# MSP430F5528ZQFE.net
KiCad netlist of a schematic drawn in Altium Designer
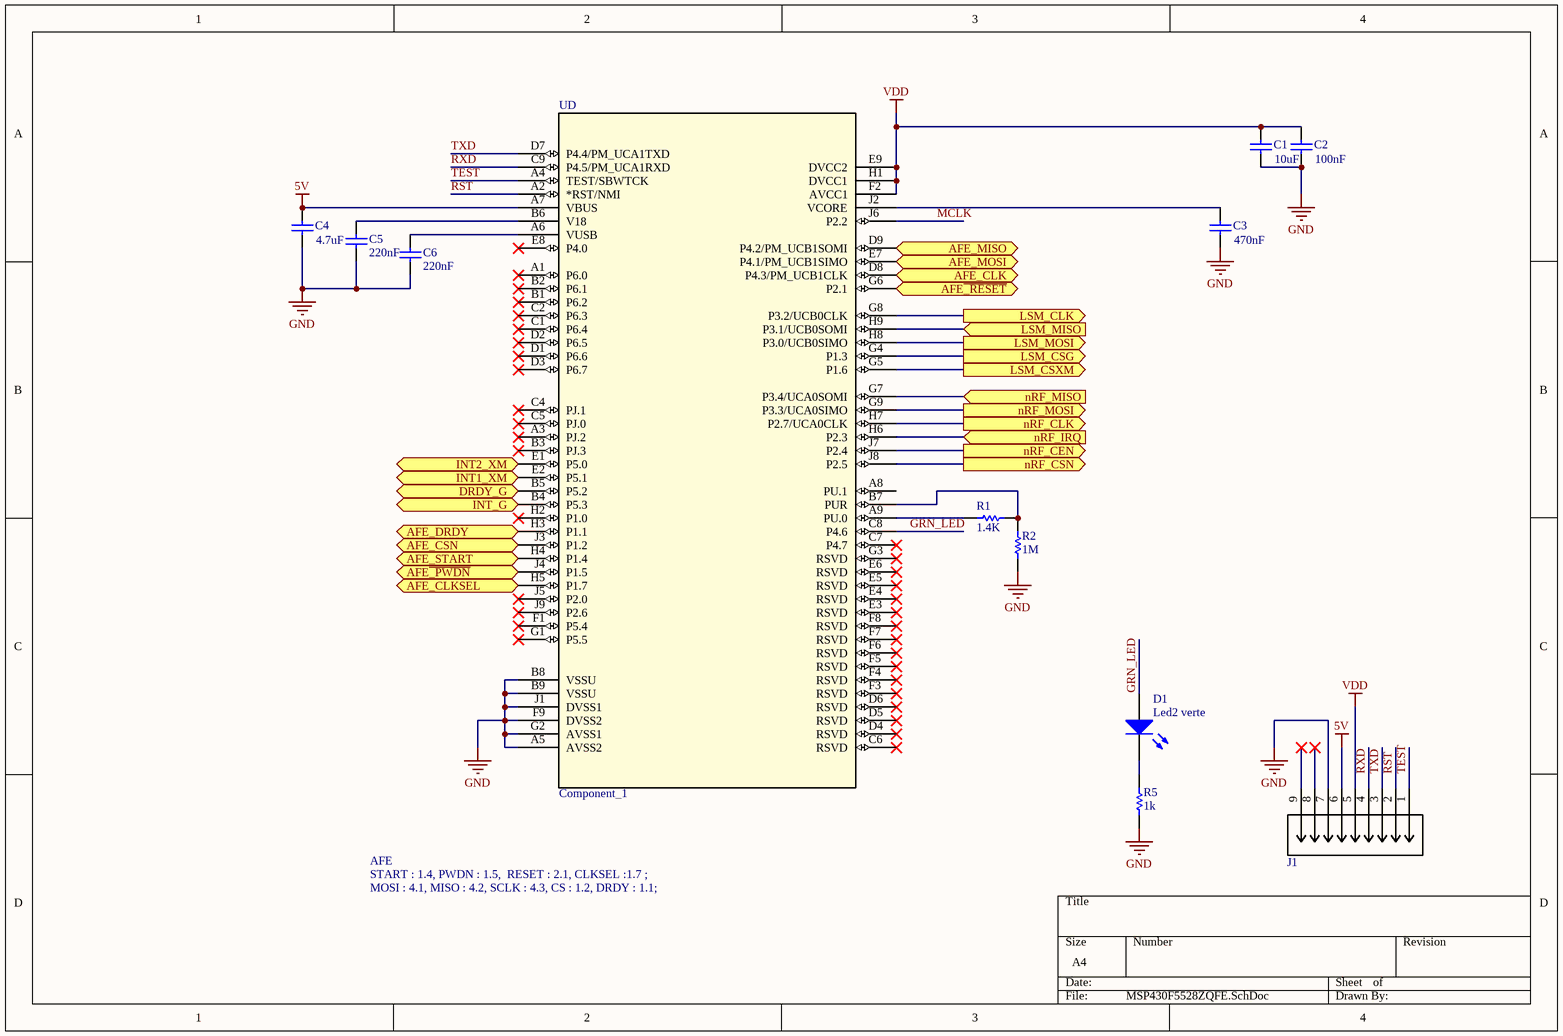
[diagram p0: MSP430F5528ZQFE.SchDoc]

(export (version "E")
  (design (tool "Eeschema 10.0.6"))
  (components
    (comp (ref "C1")
      (value "10uF")
      (footprint "0402")
      (description "Capacitor (Semiconductor SIM Model)")
      (fields (field (name "Comment") "Cap Semi") (field (name "PUBLISHER") "Altium Limited"))
      (libsource (lib "Miscellaneous Devices") (part "Cap Semi"))
    )
    (comp (ref "C2")
      (value "100nF")
      (footprint "0402")
      (description "Capacitor (Semiconductor SIM Model)")
      (fields (field (name "Comment") "Cap Semi") (field (name "PUBLISHER") "Altium Limited"))
      (libsource (lib "Miscellaneous Devices") (part "Cap Semi"))
    )
    (comp (ref "C3")
      (value "470nF")
      (footprint "0402")
      (description "Capacitor (Semiconductor SIM Model)")
      (fields (field (name "Comment") "Cap Semi") (field (name "PUBLISHER") "Altium Limited"))
      (libsource (lib "Miscellaneous Devices") (part "Cap Semi"))
    )
    (comp (ref "C4")
      (value "4.7uF")
      (footprint "0402")
      (description "Capacitor (Semiconductor SIM Model)")
      (fields (field (name "Comment") "Cap Semi") (field (name "PUBLISHER") "Altium Limited"))
      (libsource (lib "Miscellaneous Devices") (part "Cap Semi"))
    )
    (comp (ref "C5")
      (value "220nF")
      (footprint "0402")
      (description "Capacitor (Semiconductor SIM Model)")
      (fields (field (name "Comment") "Cap Semi") (field (name "PUBLISHER") "Altium Limited"))
      (libsource (lib "Miscellaneous Devices") (part "Cap Semi"))
    )
    (comp (ref "C6")
      (value "220nF")
      (footprint "0402")
      (description "Capacitor (Semiconductor SIM Model)")
      (fields (field (name "Comment") "Cap Semi") (field (name "PUBLISHER") "Altium Limited"))
      (libsource (lib "Miscellaneous Devices") (part "Cap Semi"))
    )
    (comp (ref "D1")
      (value "Led2 verte")
      (footprint "0805 (2012 metric)")
      (description "LED 2X1.2MM 570NM GN WTR CLR SMD")
      (libsource (lib "Miscellaneous Devices") (part "LED3"))
    )
    (comp (ref "J1")
      (value "FH12-7S-1SH(55)")
      (footprint "CON7_1X7_DRBF_HS")
      (description "Imported")
      (fields
        (field (name "DIGIKEYPARTNUMBER") "HFB107TR-ND")
        (field (name "COPYRIGHT") "Copyright (C) 2015 Accelerated Designs. All rights reserved")
      )
      (libsource (lib "HFB107CT-ND") (part "FH12-7S-1SH(55)"))
    )
    (comp (ref "R1")
      (value "1.4K")
      (footprint "0402")
      (description "Semiconductor Resistor")
      (fields (field (name "PUBLISHER") "Altium Limited"))
      (libsource (lib "Miscellaneous Devices") (part "Res Semi"))
    )
    (comp (ref "R2")
      (value "1M")
      (footprint "0402")
      (description "Semiconductor Resistor")
      (fields (field (name "PUBLISHER") "Altium Limited"))
      (libsource (lib "Miscellaneous Devices") (part "Res Semi"))
    )
    (comp (ref "R5")
      (value "1k")
      (footprint "0402")
      (description "Semiconductor Resistor")
      (fields (field (name "PUBLISHER") "Altium Limited"))
      (libsource (lib "Miscellaneous Devices") (part "Res Semi"))
    )
    (comp (ref "UD")
      (value "Component_1")
      (footprint "MSP430F5528ZQFE")
      (libsource (lib "MSP430F5528ZQFE") (part "Component_1"))
    )
  )
  (nets
    (net (code "1") (name "/AFE_CLK") (class "Default")
      (node (ref "UD") (pin "D8") (pinfunction "P4.3/PM_UCB1CLK_D8") (pintype "bidirectional"))
    )
    (net (code "2") (name "/AFE_CLKSEL") (class "Default")
      (node (ref "UD") (pin "H5") (pinfunction "P1.7_H5") (pintype "bidirectional"))
    )
    (net (code "3") (name "/AFE_CSN") (class "Default")
      (node (ref "UD") (pin "J3") (pinfunction "P1.2_J3") (pintype "bidirectional"))
    )
    (net (code "4") (name "/AFE_DRDY") (class "Default")
      (node (ref "UD") (pin "H3") (pinfunction "P1.1_H3") (pintype "bidirectional"))
    )
    (net (code "5") (name "/AFE_MISO") (class "Default")
      (node (ref "UD") (pin "D9") (pinfunction "P4.2/PM_UCB1SOMI_D9") (pintype "bidirectional"))
    )
    (net (code "6") (name "/AFE_MOSI") (class "Default")
      (node (ref "UD") (pin "E7") (pinfunction "P4.1/PM_UCB1SIMO_E7") (pintype "bidirectional"))
    )
    (net (code "7") (name "/AFE_START") (class "Default")
      (node (ref "UD") (pin "H4") (pinfunction "P1.4_H4") (pintype "bidirectional"))
    )
    (net (code "8") (name "/AFE~{_PWDN}") (class "Default")
      (node (ref "UD") (pin "J4") (pinfunction "P1.5_J4") (pintype "bidirectional"))
    )
    (net (code "9") (name "/AFE~{_RESET}") (class "Default")
      (node (ref "UD") (pin "G6") (pinfunction "P2.1_G6") (pintype "bidirectional"))
    )
    (net (code "10") (name "/DRDY_G") (class "Default")
      (node (ref "UD") (pin "B5") (pinfunction "P5.2_B5") (pintype "bidirectional"))
    )
    (net (code "11") (name "/GRN_LED") (class "Default")
      (node (ref "D1") (pin "1") (pinfunction "A_1") (pintype "passive"))
      (node (ref "UD") (pin "C8") (pinfunction "P4.6_C8") (pintype "bidirectional"))
    )
    (net (code "12") (name "/INT1_XM") (class "Default")
      (node (ref "UD") (pin "E2") (pinfunction "P5.1_E2") (pintype "bidirectional"))
    )
    (net (code "13") (name "/INT2_XM") (class "Default")
      (node (ref "UD") (pin "E1") (pinfunction "P5.0_E1") (pintype "bidirectional"))
    )
    (net (code "14") (name "/INT_G") (class "Default")
      (node (ref "UD") (pin "B4") (pinfunction "P5.3_B4") (pintype "bidirectional"))
    )
    (net (code "15") (name "/LSM_CLK") (class "Default")
      (node (ref "UD") (pin "G8") (pinfunction "P3.2/UCB0CLK_G8") (pintype "bidirectional"))
    )
    (net (code "16") (name "/LSM_CSG") (class "Default")
      (node (ref "UD") (pin "G4") (pinfunction "P1.3_G4") (pintype "bidirectional"))
    )
    (net (code "17") (name "/LSM_CSXM") (class "Default")
      (node (ref "UD") (pin "G5") (pinfunction "P1.6_G5") (pintype "bidirectional"))
    )
    (net (code "18") (name "/LSM_MISO") (class "Default")
      (node (ref "UD") (pin "H9") (pinfunction "P3.1/UCB0SOMI_H9") (pintype "bidirectional"))
    )
    (net (code "19") (name "/LSM_MOSI") (class "Default")
      (node (ref "UD") (pin "H8") (pinfunction "P3.0/UCB0SIMO_H8") (pintype "bidirectional"))
    )
    (net (code "20") (name "/MCLK") (class "Default")
      (node (ref "UD") (pin "J6") (pinfunction "P2.2_J6") (pintype "bidirectional"))
    )
    (net (code "21") (name "/RST") (class "Default")
      (node (ref "J1") (pin "2") (pinfunction "2_2") (pintype "passive"))
      (node (ref "UD") (pin "A2") (pinfunction "*RST/NMI_A2") (pintype "bidirectional"))
    )
    (net (code "22") (name "/RXD") (class "Default")
      (node (ref "J1") (pin "4") (pinfunction "4_4") (pintype "passive"))
      (node (ref "UD") (pin "C9") (pinfunction "P4.5/PM_UCA1RXD_C9") (pintype "bidirectional"))
    )
    (net (code "23") (name "/TEST") (class "Default")
      (node (ref "J1") (pin "1") (pinfunction "1_1") (pintype "passive"))
      (node (ref "UD") (pin "A4") (pinfunction "TEST/SBWTCK_A4") (pintype "bidirectional"))
    )
    (net (code "24") (name "/TXD") (class "Default")
      (node (ref "J1") (pin "3") (pinfunction "3_3") (pintype "passive"))
      (node (ref "UD") (pin "D7") (pinfunction "P4.4/PM_UCA1TXD_D7") (pintype "bidirectional"))
    )
    (net (code "25") (name "/nRF_CEN") (class "Default")
      (node (ref "UD") (pin "J7") (pinfunction "P2.4_J7") (pintype "bidirectional"))
    )
    (net (code "26") (name "/nRF_CLK") (class "Default")
      (node (ref "UD") (pin "H7") (pinfunction "P2.7/UCA0CLK_H7") (pintype "bidirectional"))
    )
    (net (code "27") (name "/nRF_CSN") (class "Default")
      (node (ref "UD") (pin "J8") (pinfunction "P2.5_J8") (pintype "bidirectional"))
    )
    (net (code "28") (name "/nRF_IRQ") (class "Default")
      (node (ref "UD") (pin "H6") (pinfunction "P2.3_H6") (pintype "bidirectional"))
    )
    (net (code "29") (name "/nRF_MISO") (class "Default")
      (node (ref "UD") (pin "G7") (pinfunction "P3.4/UCA0SOMI_G7") (pintype "bidirectional"))
    )
    (net (code "30") (name "/nRF_MOSI") (class "Default")
      (node (ref "UD") (pin "G9") (pinfunction "P3.3/UCA0SIMO_G9") (pintype "bidirectional"))
    )
    (net (code "31") (name "5V") (class "Default")
      (node (ref "C4") (pin "1") (pinfunction "1_1") (pintype "passive"))
      (node (ref "J1") (pin "6") (pinfunction "6_6") (pintype "passive"))
      (node (ref "UD") (pin "A7") (pinfunction "VBUS_A7") (pintype "power_in"))
    )
    (net (code "32") (name "GND") (class "Default")
      (node (ref "C1") (pin "2") (pinfunction "2_2") (pintype "passive"))
      (node (ref "C2") (pin "2") (pinfunction "2_2") (pintype "passive"))
      (node (ref "C3") (pin "2") (pinfunction "2_2") (pintype "passive"))
      (node (ref "C4") (pin "2") (pinfunction "2_2") (pintype "passive"))
      (node (ref "C5") (pin "1") (pinfunction "1_1") (pintype "passive"))
      (node (ref "C6") (pin "1") (pinfunction "1_1") (pintype "passive"))
      (node (ref "J1") (pin "7") (pinfunction "7_7") (pintype "passive"))
      (node (ref "R2") (pin "2") (pinfunction "2_2") (pintype "passive"))
      (node (ref "R5") (pin "2") (pinfunction "2_2") (pintype "passive"))
      (node (ref "UD") (pin "A5") (pinfunction "AVSS2_A5") (pintype "power_in"))
      (node (ref "UD") (pin "B8") (pinfunction "VSSU_B8") (pintype "power_in"))
      (node (ref "UD") (pin "B9") (pinfunction "VSSU_B9") (pintype "power_in"))
      (node (ref "UD") (pin "F9") (pinfunction "DVSS2_F9") (pintype "power_in"))
      (node (ref "UD") (pin "G2") (pinfunction "AVSS1_G2") (pintype "power_in"))
      (node (ref "UD") (pin "J1") (pinfunction "DVSS1_J1") (pintype "power_in"))
    )
    (net (code "33") (name "Net-(D1-K)") (class "Default")
      (node (ref "D1") (pin "2") (pinfunction "K_2") (pintype "passive"))
      (node (ref "R5") (pin "1") (pinfunction "1_1") (pintype "passive"))
    )
    (net (code "34") (name "Net-(UD-PU.0)") (class "Default")
      (node (ref "R1") (pin "2") (pinfunction "2_2") (pintype "passive"))
      (node (ref "UD") (pin "A9") (pinfunction "PU.0_A9") (pintype "bidirectional"))
    )
    (net (code "35") (name "Net-(UD-PUR)") (class "Default")
      (node (ref "R1") (pin "1") (pinfunction "1_1") (pintype "passive"))
      (node (ref "R2") (pin "1") (pinfunction "1_1") (pintype "passive"))
      (node (ref "UD") (pin "B7") (pinfunction "PUR_B7") (pintype "bidirectional"))
    )
    (net (code "36") (name "Net-(UD-V18)") (class "Default")
      (node (ref "C5") (pin "2") (pinfunction "2_2") (pintype "passive"))
      (node (ref "UD") (pin "B6") (pinfunction "V18_B6") (pintype "power_in"))
    )
    (net (code "37") (name "Net-(UD-VCORE)") (class "Default")
      (node (ref "C3") (pin "1") (pinfunction "1_1") (pintype "passive"))
      (node (ref "UD") (pin "J2") (pinfunction "VCORE_J2") (pintype "power_in"))
    )
    (net (code "38") (name "Net-(UD-VUSB)") (class "Default")
      (node (ref "C6") (pin "2") (pinfunction "2_2") (pintype "passive"))
      (node (ref "UD") (pin "A6") (pinfunction "VUSB_A6") (pintype "power_in"))
    )
    (net (code "39") (name "VDD") (class "Default")
      (node (ref "C1") (pin "1") (pinfunction "1_1") (pintype "passive"))
      (node (ref "C2") (pin "1") (pinfunction "1_1") (pintype "passive"))
      (node (ref "J1") (pin "5") (pinfunction "5_5") (pintype "passive"))
      (node (ref "UD") (pin "E9") (pinfunction "DVCC2_E9") (pintype "power_in"))
      (node (ref "UD") (pin "F2") (pinfunction "AVCC1_F2") (pintype "power_in"))
      (node (ref "UD") (pin "H1") (pinfunction "DVCC1_H1") (pintype "power_in"))
    )
    (net (code "40") (name "unconnected-(J1-Pad8)") (class "Default")
      (node (ref "J1") (pin "8") (pinfunction "8_8") (pintype "passive+no_connect"))
    )
    (net (code "41") (name "unconnected-(J1-Pad9)") (class "Default")
      (node (ref "J1") (pin "9") (pinfunction "9_9") (pintype "passive+no_connect"))
    )
    (net (code "42") (name "unconnected-(UD-P1.0-PadH2)") (class "Default")
      (node (ref "UD") (pin "H2") (pinfunction "P1.0_H2") (pintype "bidirectional+no_connect"))
    )
    (net (code "43") (name "unconnected-(UD-P2.0-PadJ5)") (class "Default")
      (node (ref "UD") (pin "J5") (pinfunction "P2.0_J5") (pintype "bidirectional+no_connect"))
    )
    (net (code "44") (name "unconnected-(UD-P2.6-PadJ9)") (class "Default")
      (node (ref "UD") (pin "J9") (pinfunction "P2.6_J9") (pintype "bidirectional+no_connect"))
    )
    (net (code "45") (name "unconnected-(UD-P4.0-PadE8)") (class "Default")
      (node (ref "UD") (pin "E8") (pinfunction "P4.0_E8") (pintype "bidirectional+no_connect"))
    )
    (net (code "46") (name "unconnected-(UD-P4.7-PadC7)") (class "Default")
      (node (ref "UD") (pin "C7") (pinfunction "P4.7_C7") (pintype "bidirectional+no_connect"))
    )
    (net (code "47") (name "unconnected-(UD-P5.4-PadF1)") (class "Default")
      (node (ref "UD") (pin "F1") (pinfunction "P5.4_F1") (pintype "bidirectional+no_connect"))
    )
    (net (code "48") (name "unconnected-(UD-P5.5-PadG1)") (class "Default")
      (node (ref "UD") (pin "G1") (pinfunction "P5.5_G1") (pintype "bidirectional+no_connect"))
    )
    (net (code "49") (name "unconnected-(UD-P6.0-PadA1)") (class "Default")
      (node (ref "UD") (pin "A1") (pinfunction "P6.0_A1") (pintype "bidirectional+no_connect"))
    )
    (net (code "50") (name "unconnected-(UD-P6.1-PadB2)") (class "Default")
      (node (ref "UD") (pin "B2") (pinfunction "P6.1_B2") (pintype "bidirectional+no_connect"))
    )
    (net (code "51") (name "unconnected-(UD-P6.2-PadB1)") (class "Default")
      (node (ref "UD") (pin "B1") (pinfunction "P6.2_B1") (pintype "bidirectional+no_connect"))
    )
    (net (code "52") (name "unconnected-(UD-P6.3-PadC2)") (class "Default")
      (node (ref "UD") (pin "C2") (pinfunction "P6.3_C2") (pintype "bidirectional+no_connect"))
    )
    (net (code "53") (name "unconnected-(UD-P6.4-PadC1)") (class "Default")
      (node (ref "UD") (pin "C1") (pinfunction "P6.4_C1") (pintype "bidirectional+no_connect"))
    )
    (net (code "54") (name "unconnected-(UD-P6.5-PadD2)") (class "Default")
      (node (ref "UD") (pin "D2") (pinfunction "P6.5_D2") (pintype "bidirectional+no_connect"))
    )
    (net (code "55") (name "unconnected-(UD-P6.6-PadD1)") (class "Default")
      (node (ref "UD") (pin "D1") (pinfunction "P6.6_D1") (pintype "bidirectional+no_connect"))
    )
    (net (code "56") (name "unconnected-(UD-P6.7-PadD3)") (class "Default")
      (node (ref "UD") (pin "D3") (pinfunction "P6.7_D3") (pintype "bidirectional+no_connect"))
    )
    (net (code "57") (name "unconnected-(UD-PJ.0-PadC5)") (class "Default")
      (node (ref "UD") (pin "C5") (pinfunction "PJ.0_C5") (pintype "bidirectional+no_connect"))
    )
    (net (code "58") (name "unconnected-(UD-PJ.1-PadC4)") (class "Default")
      (node (ref "UD") (pin "C4") (pinfunction "PJ.1_C4") (pintype "bidirectional+no_connect"))
    )
    (net (code "59") (name "unconnected-(UD-PJ.2-PadA3)") (class "Default")
      (node (ref "UD") (pin "A3") (pinfunction "PJ.2_A3") (pintype "bidirectional+no_connect"))
    )
    (net (code "60") (name "unconnected-(UD-PJ.3-PadB3)") (class "Default")
      (node (ref "UD") (pin "B3") (pinfunction "PJ.3_B3") (pintype "bidirectional+no_connect"))
    )
    (net (code "61") (name "unconnected-(UD-PU.1-PadA8)") (class "Default")
      (node (ref "UD") (pin "A8") (pinfunction "PU.1_A8") (pintype "bidirectional"))
    )
    (net (code "62") (name "unconnected-(UD-RSVD-PadC6)") (class "Default")
      (node (ref "UD") (pin "C6") (pinfunction "RSVD_C6") (pintype "bidirectional+no_connect"))
    )
    (net (code "63") (name "unconnected-(UD-RSVD-PadD4)") (class "Default")
      (node (ref "UD") (pin "D4") (pinfunction "RSVD_D4") (pintype "bidirectional+no_connect"))
    )
    (net (code "64") (name "unconnected-(UD-RSVD-PadD5)") (class "Default")
      (node (ref "UD") (pin "D5") (pinfunction "RSVD_D5") (pintype "bidirectional+no_connect"))
    )
    (net (code "65") (name "unconnected-(UD-RSVD-PadD6)") (class "Default")
      (node (ref "UD") (pin "D6") (pinfunction "RSVD_D6") (pintype "bidirectional+no_connect"))
    )
    (net (code "66") (name "unconnected-(UD-RSVD-PadE3)") (class "Default")
      (node (ref "UD") (pin "E3") (pinfunction "RSVD_E3") (pintype "bidirectional+no_connect"))
    )
    (net (code "67") (name "unconnected-(UD-RSVD-PadE4)") (class "Default")
      (node (ref "UD") (pin "E4") (pinfunction "RSVD_E4") (pintype "bidirectional+no_connect"))
    )
    (net (code "68") (name "unconnected-(UD-RSVD-PadE5)") (class "Default")
      (node (ref "UD") (pin "E5") (pinfunction "RSVD_E5") (pintype "bidirectional+no_connect"))
    )
    (net (code "69") (name "unconnected-(UD-RSVD-PadE6)") (class "Default")
      (node (ref "UD") (pin "E6") (pinfunction "RSVD_E6") (pintype "bidirectional+no_connect"))
    )
    (net (code "70") (name "unconnected-(UD-RSVD-PadF3)") (class "Default")
      (node (ref "UD") (pin "F3") (pinfunction "RSVD_F3") (pintype "bidirectional+no_connect"))
    )
    (net (code "71") (name "unconnected-(UD-RSVD-PadF4)") (class "Default")
      (node (ref "UD") (pin "F4") (pinfunction "RSVD_F4") (pintype "bidirectional+no_connect"))
    )
    (net (code "72") (name "unconnected-(UD-RSVD-PadF5)") (class "Default")
      (node (ref "UD") (pin "F5") (pinfunction "RSVD_F5") (pintype "bidirectional+no_connect"))
    )
    (net (code "73") (name "unconnected-(UD-RSVD-PadF6)") (class "Default")
      (node (ref "UD") (pin "F6") (pinfunction "RSVD_F6") (pintype "bidirectional+no_connect"))
    )
    (net (code "74") (name "unconnected-(UD-RSVD-PadF7)") (class "Default")
      (node (ref "UD") (pin "F7") (pinfunction "RSVD_F7") (pintype "bidirectional+no_connect"))
    )
    (net (code "75") (name "unconnected-(UD-RSVD-PadF8)") (class "Default")
      (node (ref "UD") (pin "F8") (pinfunction "RSVD_F8") (pintype "bidirectional+no_connect"))
    )
    (net (code "76") (name "unconnected-(UD-RSVD-PadG3)") (class "Default")
      (node (ref "UD") (pin "G3") (pinfunction "RSVD_G3") (pintype "bidirectional+no_connect"))
    )
  )
)
